# LPCB281_-_LIGHT_TOWER.net
KiCad netlist of a schematic drawn in Altium Designer
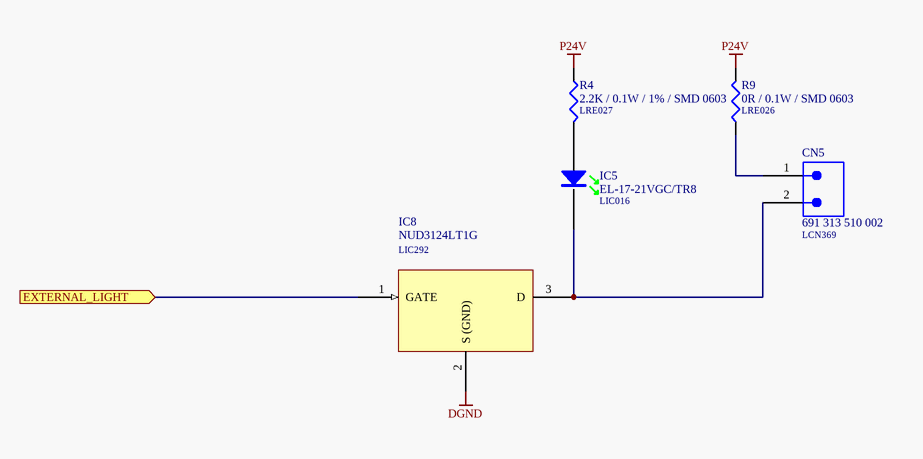
[diagram p0: LPCB281 - LIGHT TOWER.SchDoc]

(export (version "E")
  (design (tool "Eeschema 10.0.6"))
  (components
    (comp (ref "CN5")
      (value "691 313 510 002")
      (footprint "691 313 510 002")
      (description "Connector, Pluggable Terminal Block, 5.08mm, 2 Way, PTH")
      (fields (field (name "LDL_NUMBER") "LCN369"))
      (libsource (lib "LDL_Connectors") (part "691 313 510 002"))
    )
    (comp (ref "IC5")
      (value "EL-17-21VGC/TR8")
      (footprint "CR2012-0805-LED")
      (description "LED, SMD, 0805 Green [LIC016]")
      (fields (field (name "LDL_NUMBER") "LIC016"))
      (libsource (lib "LDL_Semiconductors") (part "EL-17-21VGC/TR8"))
    )
    (comp (ref "IC8")
      (value "NUD3124LT1G")
      (footprint "LFP021__SOT23")
      (description "IC, Relay Driver, 28V Industrial, SMD SOT23 [LIC292]")
      (fields (field (name "LDL_NUMBER") "LIC292"))
      (libsource (lib "LDL_Semiconductors") (part "NUD3124LT1G"))
    )
    (comp (ref "R4")
      (value "2.2K / 0.1W / 1% / SMD 0603")
      (footprint "LFP020__CR1608-0603-IPC7351_B")
      (description "Resistor, Ceramic Chip, 2.2K, 0.1W, 1%, SMD 0603 [LRE027]")
      (fields (field (name "LDL_NUMBER") "LRE027"))
      (libsource (lib "LDL_Resistors") (part "2.2K / 0.1W / 1% / SMD 0603"))
    )
    (comp (ref "R9")
      (value "0R / 0.1W / SMD 0603")
      (footprint "LFP020__CR1608-0603-IPC7351_B")
      (description "Resistor, Ceramic Chip, 0R, 0.1W, SMD 0603 [LRE026]")
      (fields (field (name "LDL_NUMBER") "LRE026"))
      (libsource (lib "LDL_Resistors") (part "0R / 0.1W / SMD 0603"))
    )
  )
  (nets
    (net (code "1") (name "/EXTERNAL_LIGHT") (class "Default")
      (node (ref "IC8") (pin "1") (pinfunction "GATE_1") (pintype "input"))
    )
    (net (code "2") (name "DGND") (class "Default")
      (node (ref "IC8") (pin "2") (pinfunction "S_(GND)_2") (pintype "passive"))
    )
    (net (code "3") (name "Net-(CN5-Pad1)") (class "Default")
      (node (ref "CN5") (pin "1") (pinfunction "1_1") (pintype "passive"))
      (node (ref "R9") (pin "1") (pintype "passive"))
    )
    (net (code "4") (name "Net-(IC5-PadA)") (class "Default")
      (node (ref "IC5") (pin "A") (pintype "passive"))
      (node (ref "R4") (pin "2") (pintype "passive"))
    )
    (net (code "5") (name "Net-(IC8-D)") (class "Default")
      (node (ref "CN5") (pin "2") (pinfunction "2_2") (pintype "passive"))
      (node (ref "IC5") (pin "K") (pintype "passive"))
      (node (ref "IC8") (pin "3") (pinfunction "D_3") (pintype "passive"))
    )
    (net (code "6") (name "P24V") (class "Default")
      (node (ref "R4") (pin "1") (pintype "passive"))
      (node (ref "R9") (pin "2") (pintype "passive"))
    )
  )
)
